# c64-stripefixvidbuf_v0_1.net
KiCad netlist of a schematic drawn in EAGLE
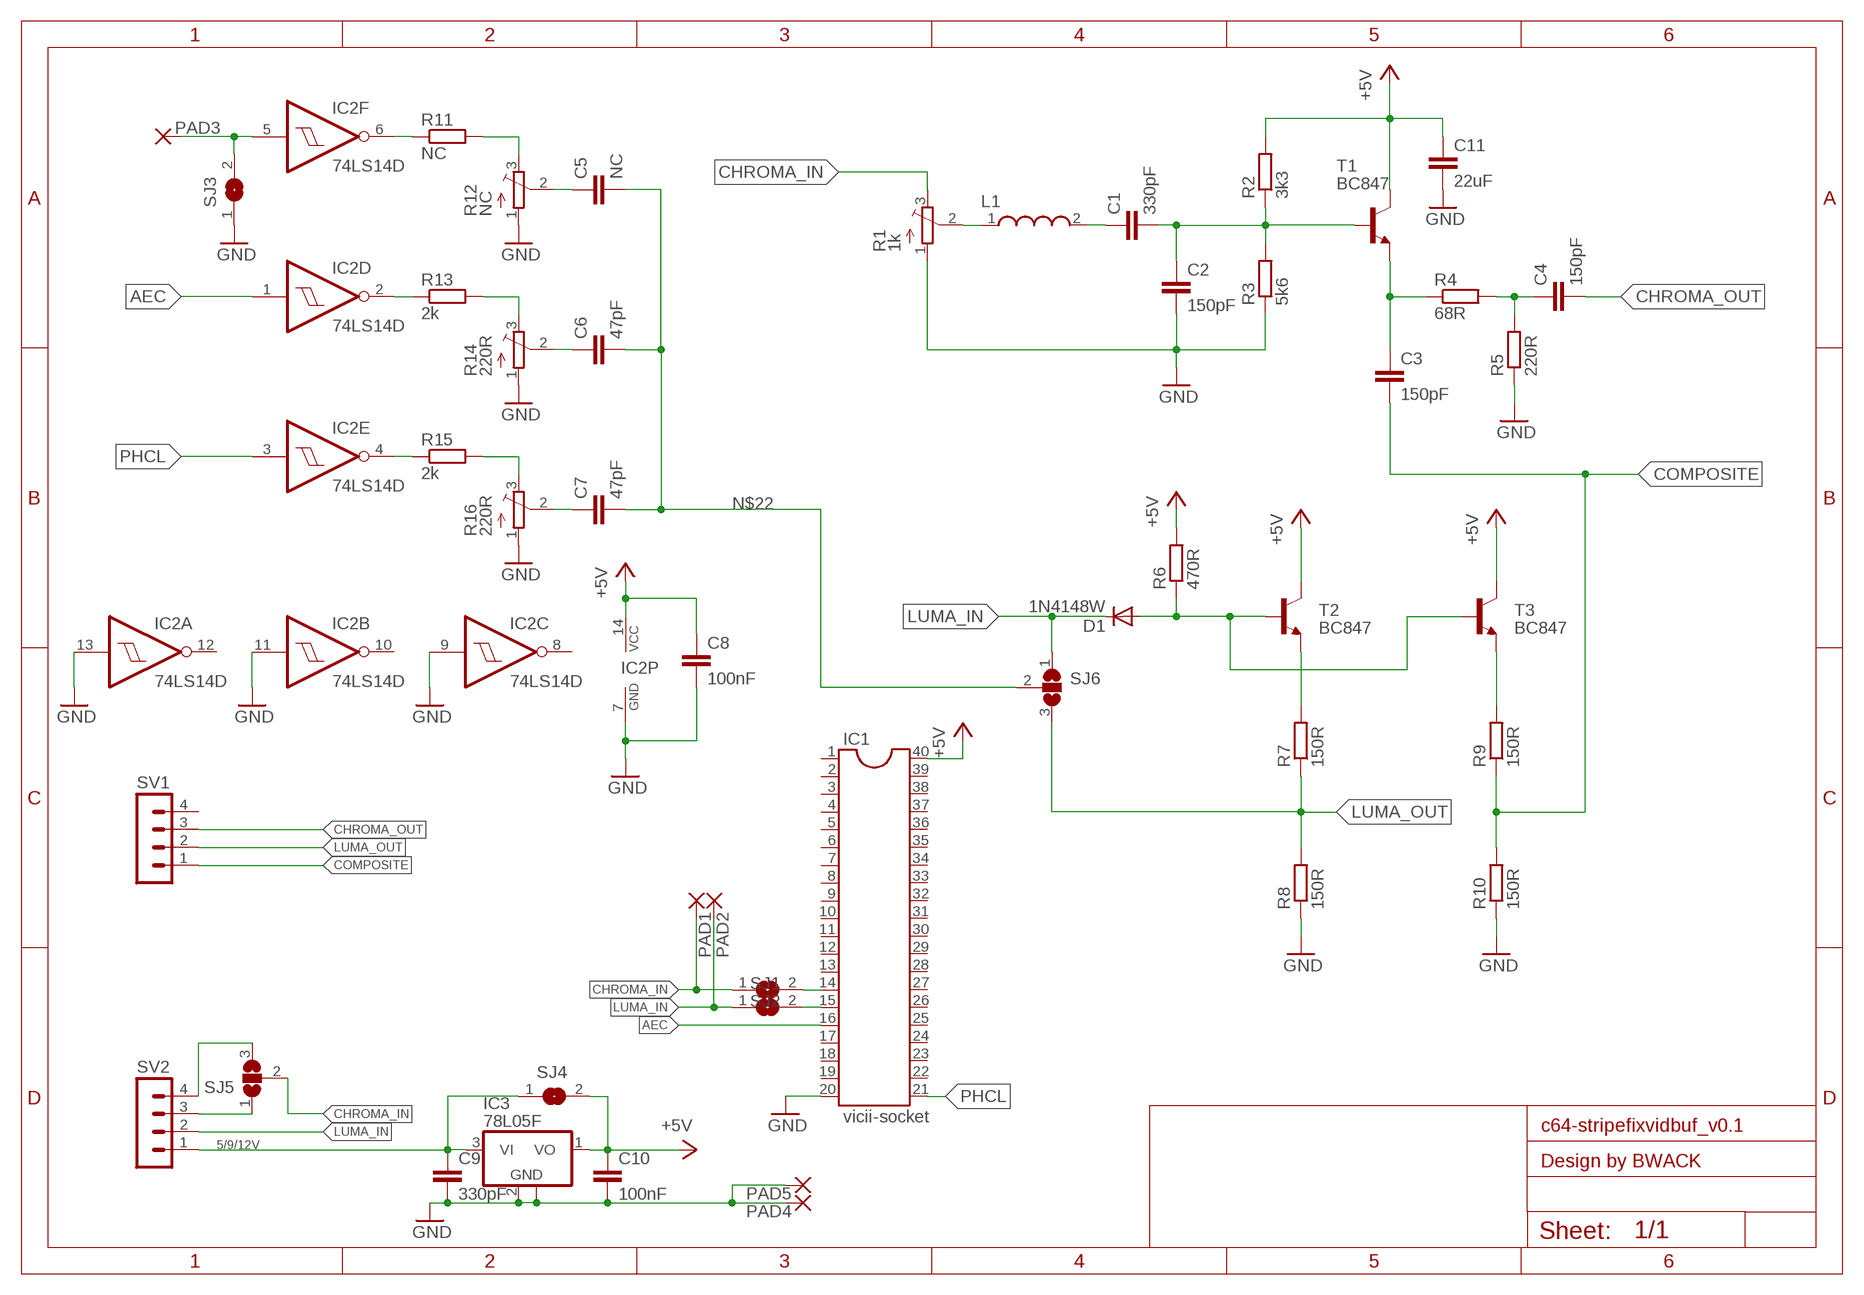
[diagram p0: schematic, sheet 1]

(export (version "E")
  (design (tool "Eeschema 10.0.6"))
  (components
    (comp (ref "C1")
      (value "330pF")
      (footprint "eagle-import:C0603")
      (libsource (lib "eagle-import") (part "C-EUC0603"))
    )
    (comp (ref "C2")
      (value "150pF")
      (footprint "eagle-import:C0603")
      (libsource (lib "eagle-import") (part "C-EUC0603"))
    )
    (comp (ref "C3")
      (value "150pF")
      (footprint "eagle-import:C0603")
      (libsource (lib "eagle-import") (part "C-EUC0603"))
    )
    (comp (ref "C4")
      (value "150pF")
      (footprint "eagle-import:C0603")
      (libsource (lib "eagle-import") (part "C-EUC0603"))
    )
    (comp (ref "C5")
      (value "NC")
      (footprint "eagle-import:C0603")
      (libsource (lib "eagle-import") (part "C-EUC0603"))
    )
    (comp (ref "C6")
      (value "47pF")
      (footprint "eagle-import:C0603")
      (libsource (lib "eagle-import") (part "C-EUC0603"))
    )
    (comp (ref "C7")
      (value "47pF")
      (footprint "eagle-import:C0603")
      (libsource (lib "eagle-import") (part "C-EUC0603"))
    )
    (comp (ref "C8")
      (value "100nF")
      (footprint "eagle-import:C0603")
      (libsource (lib "eagle-import") (part "C-EUC0603"))
    )
    (comp (ref "C9")
      (value "330pF")
      (footprint "eagle-import:C0603")
      (libsource (lib "eagle-import") (part "C-EUC0603"))
    )
    (comp (ref "C10")
      (value "100nF")
      (footprint "eagle-import:C0603")
      (libsource (lib "eagle-import") (part "C-EUC0603"))
    )
    (comp (ref "C11")
      (value "22uF")
      (footprint "eagle-import:C1206")
      (libsource (lib "eagle-import") (part "C-EUC1206"))
    )
    (comp (ref "D1")
      (value "1N4148W")
      (footprint "eagle-import:SOD123")
      (libsource (lib "eagle-import") (part "1N4148W"))
    )
    (comp (ref "IC1")
      (value "vicii-socket")
      (footprint "eagle-import:DIL40SPECIAL")
      (libsource (lib "eagle-import") (part "DIL40SPECIAL"))
    )
    (comp (ref "IC2")
      (value "74LS14D")
      (footprint "eagle-import:SO14")
      (libsource (lib "eagle-import") (part "7414DLS"))
    )
    (comp (ref "IC3")
      (value "78L05F")
      (footprint "eagle-import:SOT89")
      (libsource (lib "eagle-import") (part "78LF05"))
    )
    (comp (ref "L1")
      (value "WE-KIHQ_0805")
      (footprint "eagle-import:WE-KI_0805_B")
      (libsource (lib "eagle-import") (part "WE-KIHQ_0805"))
    )
    (comp (ref "PAD1")
      (value "SMD2")
      (footprint "eagle-import:SMD1,27-2,54")
      (libsource (lib "eagle-import") (part "SMD2"))
    )
    (comp (ref "PAD2")
      (value "SMD2")
      (footprint "eagle-import:SMD1,27-2,54")
      (libsource (lib "eagle-import") (part "SMD2"))
    )
    (comp (ref "PAD3")
      (value "SMD2")
      (footprint "eagle-import:SMD1,27-2,54")
      (libsource (lib "eagle-import") (part "SMD2"))
    )
    (comp (ref "PAD4")
      (value "2,15/1,0")
      (footprint "eagle-import:2,15_1,0")
      (libsource (lib "eagle-import") (part "2,15/1,0"))
    )
    (comp (ref "PAD5")
      (value "2,15/1,0")
      (footprint "eagle-import:2,15_1,0")
      (libsource (lib "eagle-import") (part "2,15/1,0"))
    )
    (comp (ref "R1")
      (value "1k")
      (footprint "eagle-import:TC33")
      (libsource (lib "eagle-import") (part "TRIM_EU-TC33"))
    )
    (comp (ref "R2")
      (value "3k3")
      (footprint "eagle-import:R0603")
      (libsource (lib "eagle-import") (part "R-EU_R0603"))
    )
    (comp (ref "R3")
      (value "5k6")
      (footprint "eagle-import:R0603")
      (libsource (lib "eagle-import") (part "R-EU_R0603"))
    )
    (comp (ref "R4")
      (value "68R")
      (footprint "eagle-import:R0603")
      (libsource (lib "eagle-import") (part "R-EU_R0603"))
    )
    (comp (ref "R5")
      (value "220R")
      (footprint "eagle-import:R0603")
      (libsource (lib "eagle-import") (part "R-EU_R0603"))
    )
    (comp (ref "R6")
      (value "470R")
      (footprint "eagle-import:R0603")
      (libsource (lib "eagle-import") (part "R-EU_R0603"))
    )
    (comp (ref "R7")
      (value "150R")
      (footprint "eagle-import:R0603")
      (libsource (lib "eagle-import") (part "R-EU_R0603"))
    )
    (comp (ref "R8")
      (value "150R")
      (footprint "eagle-import:R0603")
      (libsource (lib "eagle-import") (part "R-EU_R0603"))
    )
    (comp (ref "R9")
      (value "150R")
      (footprint "eagle-import:R0603")
      (libsource (lib "eagle-import") (part "R-EU_R0603"))
    )
    (comp (ref "R10")
      (value "150R")
      (footprint "eagle-import:R0603")
      (libsource (lib "eagle-import") (part "R-EU_R0603"))
    )
    (comp (ref "R11")
      (value "NC")
      (footprint "eagle-import:R0603")
      (libsource (lib "eagle-import") (part "R-EU_R0603"))
    )
    (comp (ref "R12")
      (value "NC")
      (footprint "eagle-import:TC33")
      (libsource (lib "eagle-import") (part "TRIM_EU-TC33"))
    )
    (comp (ref "R13")
      (value "2k")
      (footprint "eagle-import:R0603")
      (libsource (lib "eagle-import") (part "R-EU_R0603"))
    )
    (comp (ref "R14")
      (value "220R")
      (footprint "eagle-import:TC33")
      (libsource (lib "eagle-import") (part "TRIM_EU-TC33"))
    )
    (comp (ref "R15")
      (value "2k")
      (footprint "eagle-import:R0603")
      (libsource (lib "eagle-import") (part "R-EU_R0603"))
    )
    (comp (ref "R16")
      (value "220R")
      (footprint "eagle-import:TC33")
      (libsource (lib "eagle-import") (part "TRIM_EU-TC33"))
    )
    (comp (ref "SJ1") (value "SJ") (footprint "eagle-import:SJ") (libsource (lib "eagle-import") (part "SJ")))
    (comp (ref "SJ2") (value "SJ") (footprint "eagle-import:SJ") (libsource (lib "eagle-import") (part "SJ")))
    (comp (ref "SJ3") (value "SJ") (footprint "eagle-import:SJ") (libsource (lib "eagle-import") (part "SJ")))
    (comp (ref "SJ4") (value "SJ") (footprint "eagle-import:SJ") (libsource (lib "eagle-import") (part "SJ")))
    (comp (ref "SJ5")
      (value "SJ2W")
      (footprint "eagle-import:SJ_2")
      (libsource (lib "eagle-import") (part "SJ2W"))
    )
    (comp (ref "SJ6")
      (value "SJ2W")
      (footprint "eagle-import:SJ_2")
      (libsource (lib "eagle-import") (part "SJ2W"))
    )
    (comp (ref "SV1")
      (value "MA04-1")
      (footprint "eagle-import:MA04-1")
      (fields (field (name "OC_FARNELL") "unknown") (field (name "OC_NEWARK") "unknown"))
      (libsource (lib "eagle-import") (part "MA04-1"))
    )
    (comp (ref "SV2")
      (value "MA04-1")
      (footprint "eagle-import:MA04-1")
      (libsource (lib "eagle-import") (part "MA04-1"))
    )
    (comp (ref "T1")
      (value "BC847")
      (footprint "eagle-import:SOT23")
      (libsource (lib "eagle-import") (part "BC847"))
    )
    (comp (ref "T2")
      (value "BC847")
      (footprint "eagle-import:SOT23")
      (libsource (lib "eagle-import") (part "BC847"))
    )
    (comp (ref "T3")
      (value "BC847")
      (footprint "eagle-import:SOT23")
      (libsource (lib "eagle-import") (part "BC847"))
    )
  )
  (nets
    (net (code "1") (name "+5V") (class "Default")
      (node (ref "C10") (pin "1") (pinfunction "1_1") (pintype "passive"))
      (node (ref "C11") (pin "1") (pinfunction "1_1") (pintype "passive"))
      (node (ref "C8") (pin "1") (pinfunction "1_1") (pintype "passive"))
      (node (ref "IC1") (pin "40") (pinfunction "40_40") (pintype "passive"))
      (node (ref "IC2") (pin "14") (pinfunction "VCC_14") (pintype "power_in"))
      (node (ref "IC3") (pin "1") (pinfunction "VO_1") (pintype "passive"))
      (node (ref "R2") (pin "2") (pinfunction "2_2") (pintype "passive"))
      (node (ref "R6") (pin "2") (pinfunction "2_2") (pintype "passive"))
      (node (ref "SJ4") (pin "2") (pinfunction "2_2") (pintype "passive"))
      (node (ref "T1") (pin "3") (pinfunction "C_3") (pintype "passive"))
      (node (ref "T2") (pin "3") (pinfunction "C_3") (pintype "passive"))
      (node (ref "T3") (pin "3") (pinfunction "C_3") (pintype "passive"))
    )
    (net (code "2") (name "/5{slash}9{slash}12V") (class "Default")
      (node (ref "C9") (pin "1") (pinfunction "1_1") (pintype "passive"))
      (node (ref "IC3") (pin "3") (pinfunction "VI_3") (pintype "input"))
      (node (ref "SJ4") (pin "1") (pinfunction "1_1") (pintype "passive"))
      (node (ref "SV2") (pin "1") (pinfunction "1_1") (pintype "passive"))
    )
    (net (code "3") (name "/N$22") (class "Default")
      (node (ref "C5") (pin "2") (pinfunction "2_2") (pintype "passive"))
      (node (ref "C6") (pin "2") (pinfunction "2_2") (pintype "passive"))
      (node (ref "C7") (pin "2") (pinfunction "2_2") (pintype "passive"))
      (node (ref "SJ6") (pin "2") (pinfunction "2_2") (pintype "passive"))
    )
    (net (code "4") (name "AEC") (class "Default")
      (node (ref "IC1") (pin "16") (pinfunction "16_16") (pintype "passive"))
      (node (ref "IC2") (pin "1") (pinfunction "I_1") (pintype "input"))
    )
    (net (code "5") (name "CHROMA_IN") (class "Default")
      (node (ref "PAD1") (pin "1") (pinfunction "P_1") (pintype "passive"))
      (node (ref "R1") (pin "3") (pinfunction "E_3") (pintype "passive"))
      (node (ref "SJ1") (pin "1") (pinfunction "1_1") (pintype "passive"))
      (node (ref "SJ5") (pin "2") (pinfunction "2_2") (pintype "passive"))
    )
    (net (code "6") (name "CHROMA_OUT") (class "Default")
      (node (ref "C4") (pin "2") (pinfunction "2_2") (pintype "passive"))
      (node (ref "SV1") (pin "3") (pinfunction "3_3") (pintype "passive"))
    )
    (net (code "7") (name "COMPOSITE") (class "Default")
      (node (ref "C3") (pin "2") (pinfunction "2_2") (pintype "passive"))
      (node (ref "R10") (pin "2") (pinfunction "2_2") (pintype "passive"))
      (node (ref "R9") (pin "1") (pinfunction "1_1") (pintype "passive"))
      (node (ref "SV1") (pin "1") (pinfunction "1_1") (pintype "passive"))
    )
    (net (code "8") (name "GND") (class "Default")
      (node (ref "C10") (pin "2") (pinfunction "2_2") (pintype "passive"))
      (node (ref "C11") (pin "2") (pinfunction "2_2") (pintype "passive"))
      (node (ref "C2") (pin "2") (pinfunction "2_2") (pintype "passive"))
      (node (ref "C8") (pin "2") (pinfunction "2_2") (pintype "passive"))
      (node (ref "C9") (pin "2") (pinfunction "2_2") (pintype "passive"))
      (node (ref "IC1") (pin "20") (pinfunction "20_20") (pintype "passive"))
      (node (ref "IC2") (pin "11") (pinfunction "I_11") (pintype "input"))
      (node (ref "IC2") (pin "13") (pinfunction "I_13") (pintype "input"))
      (node (ref "IC2") (pin "7") (pinfunction "GND_7") (pintype "power_in"))
      (node (ref "IC2") (pin "9") (pinfunction "I_9") (pintype "input"))
      (node (ref "IC3") (pin "2") (pinfunction "GND_2") (pintype "passive"))
      (node (ref "IC3") (pin "2@1") (pinfunction "GND_2@1") (pintype "passive"))
      (node (ref "PAD4") (pin "1") (pinfunction "P_1") (pintype "passive"))
      (node (ref "PAD5") (pin "1") (pinfunction "P_1") (pintype "passive"))
      (node (ref "R1") (pin "1") (pinfunction "A_1") (pintype "passive"))
      (node (ref "R10") (pin "1") (pinfunction "1_1") (pintype "passive"))
      (node (ref "R12") (pin "1") (pinfunction "A_1") (pintype "passive"))
      (node (ref "R14") (pin "1") (pinfunction "A_1") (pintype "passive"))
      (node (ref "R16") (pin "1") (pinfunction "A_1") (pintype "passive"))
      (node (ref "R3") (pin "1") (pinfunction "1_1") (pintype "passive"))
      (node (ref "R5") (pin "1") (pinfunction "1_1") (pintype "passive"))
      (node (ref "R8") (pin "1") (pinfunction "1_1") (pintype "passive"))
      (node (ref "SJ3") (pin "1") (pinfunction "1_1") (pintype "passive"))
    )
    (net (code "9") (name "LUMA_IN") (class "Default")
      (node (ref "D1") (pin "C") (pinfunction "C_C") (pintype "passive"))
      (node (ref "PAD2") (pin "1") (pinfunction "P_1") (pintype "passive"))
      (node (ref "SJ2") (pin "1") (pinfunction "1_1") (pintype "passive"))
      (node (ref "SJ6") (pin "1") (pinfunction "1_1") (pintype "passive"))
      (node (ref "SV2") (pin "2") (pinfunction "2_2") (pintype "passive"))
    )
    (net (code "10") (name "LUMA_OUT") (class "Default")
      (node (ref "R7") (pin "1") (pinfunction "1_1") (pintype "passive"))
      (node (ref "R8") (pin "2") (pinfunction "2_2") (pintype "passive"))
      (node (ref "SJ6") (pin "3") (pinfunction "3_3") (pintype "passive"))
      (node (ref "SV1") (pin "2") (pinfunction "2_2") (pintype "passive"))
    )
    (net (code "11") (name "Net-(C1-Pad1)") (class "Default")
      (node (ref "C1") (pin "1") (pinfunction "1_1") (pintype "passive"))
      (node (ref "L1") (pin "2") (pinfunction "2_2") (pintype "passive"))
    )
    (net (code "12") (name "Net-(C4-Pad1)") (class "Default")
      (node (ref "C4") (pin "1") (pinfunction "1_1") (pintype "passive"))
      (node (ref "R4") (pin "2") (pinfunction "2_2") (pintype "passive"))
      (node (ref "R5") (pin "2") (pinfunction "2_2") (pintype "passive"))
    )
    (net (code "13") (name "Net-(IC1-Pad14)") (class "Default")
      (node (ref "IC1") (pin "14") (pinfunction "14_14") (pintype "passive"))
      (node (ref "SJ1") (pin "2") (pinfunction "2_2") (pintype "passive"))
    )
    (net (code "14") (name "Net-(IC1-Pad15)") (class "Default")
      (node (ref "IC1") (pin "15") (pinfunction "15_15") (pintype "passive"))
      (node (ref "SJ2") (pin "2") (pinfunction "2_2") (pintype "passive"))
    )
    (net (code "15") (name "Net-(IC2D-O)") (class "Default")
      (node (ref "IC2") (pin "2") (pinfunction "O_2") (pintype "output"))
      (node (ref "R13") (pin "1") (pinfunction "1_1") (pintype "passive"))
    )
    (net (code "16") (name "Net-(IC2E-O)") (class "Default")
      (node (ref "IC2") (pin "4") (pinfunction "O_4") (pintype "output"))
      (node (ref "R15") (pin "1") (pinfunction "1_1") (pintype "passive"))
    )
    (net (code "17") (name "Net-(IC2F-I)") (class "Default")
      (node (ref "IC2") (pin "5") (pinfunction "I_5") (pintype "input"))
      (node (ref "PAD3") (pin "1") (pinfunction "P_1") (pintype "passive"))
      (node (ref "SJ3") (pin "2") (pinfunction "2_2") (pintype "passive"))
    )
    (net (code "18") (name "Net-(IC2F-O)") (class "Default")
      (node (ref "IC2") (pin "6") (pinfunction "O_6") (pintype "output"))
      (node (ref "R11") (pin "1") (pinfunction "1_1") (pintype "passive"))
    )
    (net (code "19") (name "Net-(R1-S)") (class "Default")
      (node (ref "L1") (pin "1") (pinfunction "1_1") (pintype "passive"))
      (node (ref "R1") (pin "2") (pinfunction "S_2") (pintype "passive"))
    )
    (net (code "20") (name "Net-(R12-E)") (class "Default")
      (node (ref "R11") (pin "2") (pinfunction "2_2") (pintype "passive"))
      (node (ref "R12") (pin "3") (pinfunction "E_3") (pintype "passive"))
    )
    (net (code "21") (name "Net-(R12-S)") (class "Default")
      (node (ref "C5") (pin "1") (pinfunction "1_1") (pintype "passive"))
      (node (ref "R12") (pin "2") (pinfunction "S_2") (pintype "passive"))
    )
    (net (code "22") (name "Net-(R14-E)") (class "Default")
      (node (ref "R13") (pin "2") (pinfunction "2_2") (pintype "passive"))
      (node (ref "R14") (pin "3") (pinfunction "E_3") (pintype "passive"))
    )
    (net (code "23") (name "Net-(R14-S)") (class "Default")
      (node (ref "C6") (pin "1") (pinfunction "1_1") (pintype "passive"))
      (node (ref "R14") (pin "2") (pinfunction "S_2") (pintype "passive"))
    )
    (net (code "24") (name "Net-(R16-E)") (class "Default")
      (node (ref "R15") (pin "2") (pinfunction "2_2") (pintype "passive"))
      (node (ref "R16") (pin "3") (pinfunction "E_3") (pintype "passive"))
    )
    (net (code "25") (name "Net-(R16-S)") (class "Default")
      (node (ref "C7") (pin "1") (pinfunction "1_1") (pintype "passive"))
      (node (ref "R16") (pin "2") (pinfunction "S_2") (pintype "passive"))
    )
    (net (code "26") (name "Net-(SJ5-Pad1)") (class "Default")
      (node (ref "SJ5") (pin "1") (pinfunction "1_1") (pintype "passive"))
      (node (ref "SV2") (pin "3") (pinfunction "3_3") (pintype "passive"))
    )
    (net (code "27") (name "Net-(SJ5-Pad3)") (class "Default")
      (node (ref "SJ5") (pin "3") (pinfunction "3_3") (pintype "passive"))
      (node (ref "SV2") (pin "4") (pinfunction "4_4") (pintype "passive"))
    )
    (net (code "28") (name "Net-(T1-B)") (class "Default")
      (node (ref "C1") (pin "2") (pinfunction "2_2") (pintype "passive"))
      (node (ref "C2") (pin "1") (pinfunction "1_1") (pintype "passive"))
      (node (ref "R2") (pin "1") (pinfunction "1_1") (pintype "passive"))
      (node (ref "R3") (pin "2") (pinfunction "2_2") (pintype "passive"))
      (node (ref "T1") (pin "1") (pinfunction "B_1") (pintype "passive"))
    )
    (net (code "29") (name "Net-(T1-E)") (class "Default")
      (node (ref "C3") (pin "1") (pinfunction "1_1") (pintype "passive"))
      (node (ref "R4") (pin "1") (pinfunction "1_1") (pintype "passive"))
      (node (ref "T1") (pin "2") (pinfunction "E_2") (pintype "passive"))
    )
    (net (code "30") (name "Net-(T2-B)") (class "Default")
      (node (ref "D1") (pin "A") (pinfunction "A_A") (pintype "passive"))
      (node (ref "R6") (pin "1") (pinfunction "1_1") (pintype "passive"))
      (node (ref "T2") (pin "1") (pinfunction "B_1") (pintype "passive"))
      (node (ref "T3") (pin "1") (pinfunction "B_1") (pintype "passive"))
    )
    (net (code "31") (name "Net-(T2-E)") (class "Default")
      (node (ref "R7") (pin "2") (pinfunction "2_2") (pintype "passive"))
      (node (ref "T2") (pin "2") (pinfunction "E_2") (pintype "passive"))
    )
    (net (code "32") (name "Net-(T3-E)") (class "Default")
      (node (ref "R9") (pin "2") (pinfunction "2_2") (pintype "passive"))
      (node (ref "T3") (pin "2") (pinfunction "E_2") (pintype "passive"))
    )
    (net (code "33") (name "PHCL") (class "Default")
      (node (ref "IC1") (pin "21") (pinfunction "21_21") (pintype "passive"))
      (node (ref "IC2") (pin "3") (pinfunction "I_3") (pintype "input"))
    )
    (net (code "34") (name "unconnected-(IC1-Pad1)") (class "Default")
      (node (ref "IC1") (pin "1") (pinfunction "1_1") (pintype "passive"))
    )
    (net (code "35") (name "unconnected-(IC1-Pad2)") (class "Default")
      (node (ref "IC1") (pin "2") (pinfunction "2_2") (pintype "passive"))
    )
    (net (code "36") (name "unconnected-(IC1-Pad3)") (class "Default")
      (node (ref "IC1") (pin "3") (pinfunction "3_3") (pintype "passive"))
    )
    (net (code "37") (name "unconnected-(IC1-Pad4)") (class "Default")
      (node (ref "IC1") (pin "4") (pinfunction "4_4") (pintype "passive"))
    )
    (net (code "38") (name "unconnected-(IC1-Pad5)") (class "Default")
      (node (ref "IC1") (pin "5") (pinfunction "5_5") (pintype "passive"))
    )
    (net (code "39") (name "unconnected-(IC1-Pad6)") (class "Default")
      (node (ref "IC1") (pin "6") (pinfunction "6_6") (pintype "passive"))
    )
    (net (code "40") (name "unconnected-(IC1-Pad7)") (class "Default")
      (node (ref "IC1") (pin "7") (pinfunction "7_7") (pintype "passive"))
    )
    (net (code "41") (name "unconnected-(IC1-Pad8)") (class "Default")
      (node (ref "IC1") (pin "8") (pinfunction "8_8") (pintype "passive"))
    )
    (net (code "42") (name "unconnected-(IC1-Pad9)") (class "Default")
      (node (ref "IC1") (pin "9") (pinfunction "9_9") (pintype "passive"))
    )
    (net (code "43") (name "unconnected-(IC1-Pad10)") (class "Default")
      (node (ref "IC1") (pin "10") (pinfunction "10_10") (pintype "passive"))
    )
    (net (code "44") (name "unconnected-(IC1-Pad11)") (class "Default")
      (node (ref "IC1") (pin "11") (pinfunction "11_11") (pintype "passive"))
    )
    (net (code "45") (name "unconnected-(IC1-Pad12)") (class "Default")
      (node (ref "IC1") (pin "12") (pinfunction "12_12") (pintype "passive"))
    )
    (net (code "46") (name "unconnected-(IC1-Pad13)") (class "Default")
      (node (ref "IC1") (pin "13") (pinfunction "13_13") (pintype "passive"))
    )
    (net (code "47") (name "unconnected-(IC1-Pad17)") (class "Default")
      (node (ref "IC1") (pin "17") (pinfunction "17_17") (pintype "passive"))
    )
    (net (code "48") (name "unconnected-(IC1-Pad18)") (class "Default")
      (node (ref "IC1") (pin "18") (pinfunction "18_18") (pintype "passive"))
    )
    (net (code "49") (name "unconnected-(IC1-Pad19)") (class "Default")
      (node (ref "IC1") (pin "19") (pinfunction "19_19") (pintype "passive"))
    )
    (net (code "50") (name "unconnected-(IC1-Pad22)") (class "Default")
      (node (ref "IC1") (pin "22") (pinfunction "22_22") (pintype "passive"))
    )
    (net (code "51") (name "unconnected-(IC1-Pad23)") (class "Default")
      (node (ref "IC1") (pin "23") (pinfunction "23_23") (pintype "passive"))
    )
    (net (code "52") (name "unconnected-(IC1-Pad24)") (class "Default")
      (node (ref "IC1") (pin "24") (pinfunction "24_24") (pintype "passive"))
    )
    (net (code "53") (name "unconnected-(IC1-Pad25)") (class "Default")
      (node (ref "IC1") (pin "25") (pinfunction "25_25") (pintype "passive"))
    )
    (net (code "54") (name "unconnected-(IC1-Pad26)") (class "Default")
      (node (ref "IC1") (pin "26") (pinfunction "26_26") (pintype "passive"))
    )
    (net (code "55") (name "unconnected-(IC1-Pad27)") (class "Default")
      (node (ref "IC1") (pin "27") (pinfunction "27_27") (pintype "passive"))
    )
    (net (code "56") (name "unconnected-(IC1-Pad28)") (class "Default")
      (node (ref "IC1") (pin "28") (pinfunction "28_28") (pintype "passive"))
    )
    (net (code "57") (name "unconnected-(IC1-Pad29)") (class "Default")
      (node (ref "IC1") (pin "29") (pinfunction "29_29") (pintype "passive"))
    )
    (net (code "58") (name "unconnected-(IC1-Pad30)") (class "Default")
      (node (ref "IC1") (pin "30") (pinfunction "30_30") (pintype "passive"))
    )
    (net (code "59") (name "unconnected-(IC1-Pad31)") (class "Default")
      (node (ref "IC1") (pin "31") (pinfunction "31_31") (pintype "passive"))
    )
    (net (code "60") (name "unconnected-(IC1-Pad32)") (class "Default")
      (node (ref "IC1") (pin "32") (pinfunction "32_32") (pintype "passive"))
    )
    (net (code "61") (name "unconnected-(IC1-Pad33)") (class "Default")
      (node (ref "IC1") (pin "33") (pinfunction "33_33") (pintype "passive"))
    )
    (net (code "62") (name "unconnected-(IC1-Pad34)") (class "Default")
      (node (ref "IC1") (pin "34") (pinfunction "34_34") (pintype "passive"))
    )
    (net (code "63") (name "unconnected-(IC1-Pad35)") (class "Default")
      (node (ref "IC1") (pin "35") (pinfunction "35_35") (pintype "passive"))
    )
    (net (code "64") (name "unconnected-(IC1-Pad36)") (class "Default")
      (node (ref "IC1") (pin "36") (pinfunction "36_36") (pintype "passive"))
    )
    (net (code "65") (name "unconnected-(IC1-Pad37)") (class "Default")
      (node (ref "IC1") (pin "37") (pinfunction "37_37") (pintype "passive"))
    )
    (net (code "66") (name "unconnected-(IC1-Pad38)") (class "Default")
      (node (ref "IC1") (pin "38") (pinfunction "38_38") (pintype "passive"))
    )
    (net (code "67") (name "unconnected-(IC1-Pad39)") (class "Default")
      (node (ref "IC1") (pin "39") (pinfunction "39_39") (pintype "passive"))
    )
    (net (code "68") (name "unconnected-(IC2A-O-Pad12)") (class "Default")
      (node (ref "IC2") (pin "12") (pinfunction "O_12") (pintype "output"))
    )
    (net (code "69") (name "unconnected-(IC2B-O-Pad10)") (class "Default")
      (node (ref "IC2") (pin "10") (pinfunction "O_10") (pintype "output"))
    )
    (net (code "70") (name "unconnected-(IC2C-O-Pad8)") (class "Default")
      (node (ref "IC2") (pin "8") (pinfunction "O_8") (pintype "output"))
    )
    (net (code "71") (name "unconnected-(SV1-Pad4)") (class "Default")
      (node (ref "SV1") (pin "4") (pinfunction "4_4") (pintype "passive"))
    )
  )
)
